# OpAmpSCH.net
KiCad netlist of a schematic drawn in Altium Designer
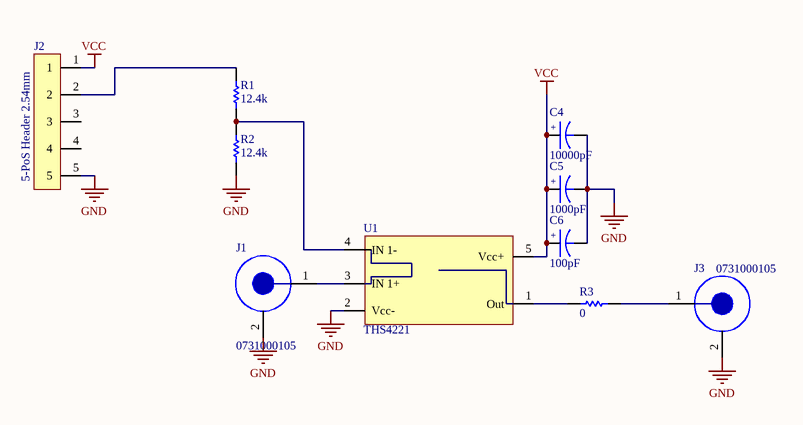
[diagram p0: OpAmpSCH.SchDoc]

(export (version "E")
  (design (tool "Eeschema 10.0.6"))
  (components
    (comp (ref "C4")
      (value "10000pF")
      (footprint "0603C")
      (description "Cap Poly")
      (libsource (lib "GENERIC_LIB") (part "CPoly"))
    )
    (comp (ref "C5")
      (value "1000pF")
      (footprint "0603C")
      (description "Cap Poly")
      (libsource (lib "GENERIC_LIB") (part "CPoly"))
    )
    (comp (ref "C6")
      (value "100pF")
      (footprint "0603C")
      (description "Cap Poly")
      (libsource (lib "GENERIC_LIB") (part "CPoly"))
    )
    (comp (ref "J1")
      (value "0731000105")
      (footprint "0731000105")
      (description "BNC Connector Jack, Female Socket 50Ohm Through Hole, Right Angle Solder")
      (libsource (lib "CON_LIB") (part "0731000105"))
    )
    (comp (ref "J2")
      (value "5-PoS Header 2.54mm")
      (footprint "2.54mm Pitch Header")
      (libsource (lib "CON_LIB") (part "5-PoS Header 2.54mm"))
    )
    (comp (ref "J3")
      (value "0731000105")
      (footprint "0731000105")
      (description "BNC Connector Jack, Female Socket 50Ohm Through Hole, Right Angle Solder")
      (libsource (lib "CON_LIB") (part "0731000105"))
    )
    (comp (ref "R1")
      (value "12.4k")
      (footprint "0603C")
      (description "Resistor")
      (fields (field (name "TOLERANCE") "5%"))
      (libsource (lib "GENERIC_LIB") (part "R"))
    )
    (comp (ref "R2")
      (value "12.4k")
      (footprint "0603C")
      (description "Resistor")
      (fields (field (name "TOLERANCE") "5%"))
      (libsource (lib "GENERIC_LIB") (part "R"))
    )
    (comp (ref "R3")
      (value "0")
      (footprint "1206C")
      (description "Resistor")
      (fields (field (name "TOLERANCE") "5%"))
      (libsource (lib "GENERIC_LIB") (part "R"))
    )
    (comp (ref "U1")
      (value "THS4221")
      (footprint "MIC920")
      (description "Voltage Feedback Amplifier 1 Circuit Rail-to-Rail")
      (libsource (lib "ANALOG_LIB") (part "THS4221"))
    )
  )
  (nets
    (net (code "1") (name "GND") (class "Default")
      (node (ref "C4") (pin "2") (pinfunction "2_2") (pintype "passive"))
      (node (ref "C5") (pin "2") (pinfunction "2_2") (pintype "passive"))
      (node (ref "C6") (pin "2") (pinfunction "2_2") (pintype "passive"))
      (node (ref "J1") (pin "2") (pinfunction "2_2") (pintype "passive"))
      (node (ref "J2") (pin "5") (pinfunction "5_5") (pintype "passive"))
      (node (ref "J3") (pin "2") (pinfunction "2_2") (pintype "passive"))
      (node (ref "R2") (pin "1") (pinfunction "1_1") (pintype "passive"))
      (node (ref "U1") (pin "2") (pinfunction "Vcc-_2") (pintype "passive"))
    )
    (net (code "2") (name "Net-(J2-Pad2)") (class "Default")
      (node (ref "J2") (pin "2") (pinfunction "2_2") (pintype "passive"))
      (node (ref "R1") (pin "2") (pinfunction "2_2") (pintype "passive"))
    )
    (net (code "3") (name "Net-(J3-Pad1)") (class "Default")
      (node (ref "J3") (pin "1") (pinfunction "1_1") (pintype "passive"))
      (node (ref "R3") (pin "2") (pinfunction "2_2") (pintype "passive"))
    )
    (net (code "4") (name "Net-(U1-IN_1+)") (class "Default")
      (node (ref "J1") (pin "1") (pinfunction "1_1") (pintype "passive"))
      (node (ref "U1") (pin "3") (pinfunction "IN_1+_3") (pintype "passive"))
    )
    (net (code "5") (name "Net-(U1-IN_1-)") (class "Default")
      (node (ref "R1") (pin "1") (pinfunction "1_1") (pintype "passive"))
      (node (ref "R2") (pin "2") (pinfunction "2_2") (pintype "passive"))
      (node (ref "U1") (pin "4") (pinfunction "IN_1-_4") (pintype "passive"))
    )
    (net (code "6") (name "Net-(U1-Out)") (class "Default")
      (node (ref "R3") (pin "1") (pinfunction "1_1") (pintype "passive"))
      (node (ref "U1") (pin "1") (pinfunction "Out_1") (pintype "passive"))
    )
    (net (code "7") (name "VCC") (class "Default")
      (node (ref "C4") (pin "1") (pinfunction "1_1") (pintype "passive"))
      (node (ref "C5") (pin "1") (pinfunction "1_1") (pintype "passive"))
      (node (ref "C6") (pin "1") (pinfunction "1_1") (pintype "passive"))
      (node (ref "J2") (pin "1") (pinfunction "1_1") (pintype "passive"))
      (node (ref "U1") (pin "5") (pinfunction "Vcc+_5") (pintype "passive"))
    )
    (net (code "8") (name "unconnected-(J2-Pad3)") (class "Default")
      (node (ref "J2") (pin "3") (pinfunction "3_3") (pintype "passive"))
    )
    (net (code "9") (name "unconnected-(J2-Pad4)") (class "Default")
      (node (ref "J2") (pin "4") (pinfunction "4_4") (pintype "passive"))
    )
  )
)
